# radio_oled.net
KiCad netlist of a schematic drawn in EAGLE
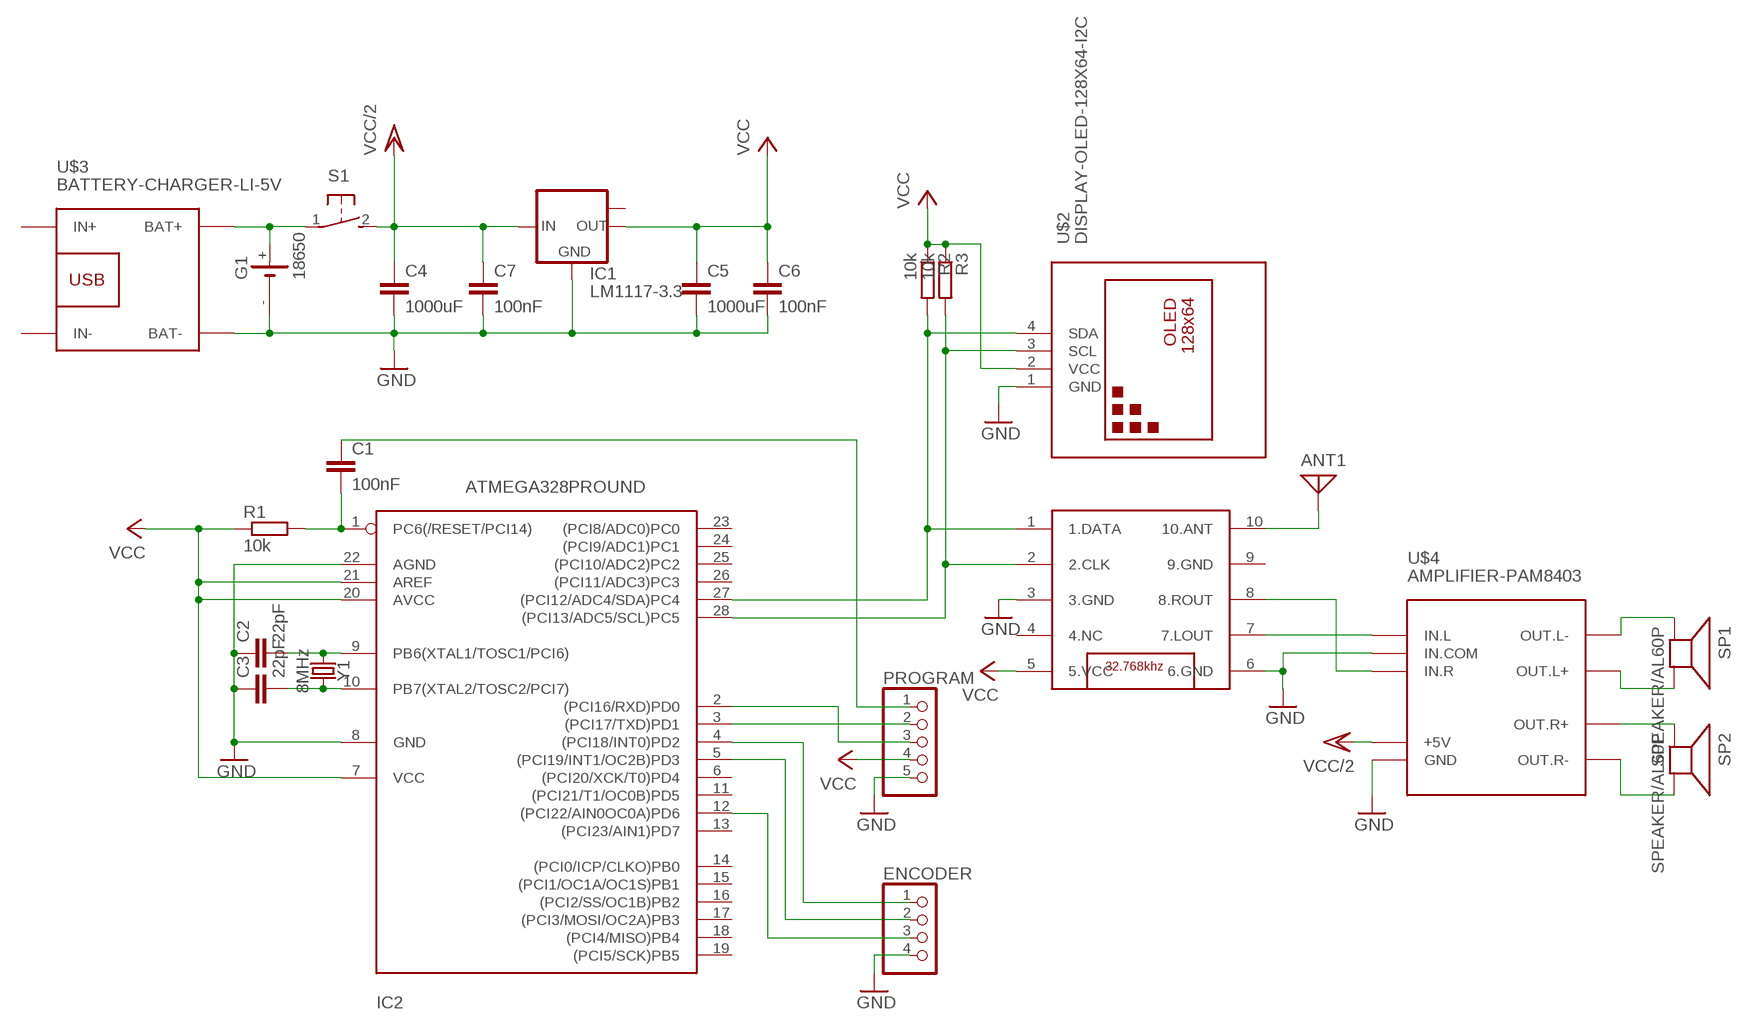
[diagram p0: schematic, sheet 1]

(export (version "E")
  (design (tool "Eeschema 10.0.6"))
  (components
    (comp (ref "ANT1")
      (value "ANTENNA")
      (footprint "eagle-import:PAD-01")
      (libsource (lib "eagle-import") (part "ANTENNA"))
    )
    (comp (ref "C1")
      (value "100nF")
      (footprint "eagle-import:C025-025X050")
      (libsource (lib "eagle-import") (part "C-EU025-025X050"))
    )
    (comp (ref "C2")
      (value "22pF")
      (footprint "eagle-import:C025-025X050")
      (libsource (lib "eagle-import") (part "C-EU025-025X050"))
    )
    (comp (ref "C3")
      (value "22pF")
      (footprint "eagle-import:C025-025X050")
      (libsource (lib "eagle-import") (part "C-EU025-025X050"))
    )
    (comp (ref "C4")
      (value "1000uF")
      (footprint "eagle-import:C025-025X050")
      (libsource (lib "eagle-import") (part "C-EU025-025X050"))
    )
    (comp (ref "C5")
      (value "1000uF")
      (footprint "eagle-import:C025-025X050")
      (libsource (lib "eagle-import") (part "C-EU025-025X050"))
    )
    (comp (ref "C6")
      (value "100nF")
      (footprint "eagle-import:C025-025X050")
      (libsource (lib "eagle-import") (part "C-EU025-025X050"))
    )
    (comp (ref "C7")
      (value "100nF")
      (footprint "eagle-import:C025-025X050")
      (libsource (lib "eagle-import") (part "C-EU025-025X050"))
    )
    (comp (ref "ENCODER")
      (value "PINHD-1X4")
      (footprint "eagle-import:1X04")
      (libsource (lib "eagle-import") (part "PINHD-1X4"))
    )
    (comp (ref "G1")
      (value "18650")
      (footprint "eagle-import:SL-160AA_PT")
      (libsource (lib "eagle-import") (part "SL-160AA/PT"))
    )
    (comp (ref "IC1")
      (value "LM1117-3.3")
      (footprint "eagle-import:SOT223")
      (libsource (lib "eagle-import") (part "LM1117IMPX-3.3"))
    )
    (comp (ref "IC2")
      (value "ATMEGA328PROUND")
      (footprint "eagle-import:DIL28-3-ROUND")
      (libsource (lib "eagle-import") (part "ATMEGA328PROUND"))
    )
    (comp (ref "PROGRAM")
      (value "PINHD-1X5")
      (footprint "eagle-import:1X05")
      (libsource (lib "eagle-import") (part "PINHD-1X5"))
    )
    (comp (ref "R1")
      (value "10k")
      (footprint "eagle-import:0204_7")
      (libsource (lib "eagle-import") (part "R-EU_0204/7"))
    )
    (comp (ref "R2")
      (value "10k")
      (footprint "eagle-import:0204_7")
      (libsource (lib "eagle-import") (part "R-EU_0204/7"))
    )
    (comp (ref "R3")
      (value "10k")
      (footprint "eagle-import:0204_7")
      (libsource (lib "eagle-import") (part "R-EU_0204/7"))
    )
    (comp (ref "S1")
      (value "31-XX")
      (footprint "eagle-import:B3F-31XX")
      (libsource (lib "eagle-import") (part "31-XX"))
    )
    (comp (ref "SP1")
      (value "SPEAKER/AL60P")
      (footprint "eagle-import:AL60P")
      (libsource (lib "eagle-import") (part "SPEAKER/AL60P"))
    )
    (comp (ref "SP2")
      (value "SPEAKER/AL60P")
      (footprint "eagle-import:AL60P")
      (libsource (lib "eagle-import") (part "SPEAKER/AL60P"))
    )
    (comp (ref "U$1")
      (value "TEA5767")
      (footprint "eagle-import:TJ-102BC")
      (libsource (lib "eagle-import") (part "TEA5767"))
    )
    (comp (ref "U$2")
      (value "DISPLAY-OLED-128X64-I2C")
      (footprint "eagle-import:DISPLAY-OLED-128X64-I2C")
      (libsource (lib "eagle-import") (part "DISPLAY-OLED-128X64-I2C"))
    )
    (comp (ref "U$3")
      (value "BATTERY-CHARGER-LI-5V")
      (footprint "eagle-import:BATTERY-CHARGER-LI-5V")
      (libsource (lib "eagle-import") (part "BATTERY-CHARGER-LI-5V"))
    )
    (comp (ref "U$4")
      (value "AMPLIFIER-PAM8403")
      (footprint "eagle-import:AMPLIFIER-PAM8403")
      (libsource (lib "eagle-import") (part "AMPLIFIER-PAM8403"))
    )
    (comp (ref "Y1")
      (value "8MHz")
      (footprint "eagle-import:HC49UP")
      (libsource (lib "eagle-import") (part "CRYSTAL-8MHZSMD-HC49UP"))
    )
  )
  (nets
    (net (code "1") (name "GND") (class "Default")
      (node (ref "C2") (pin "1") (pinfunction "1_1") (pintype "passive"))
      (node (ref "C3") (pin "1") (pinfunction "1_1") (pintype "passive"))
      (node (ref "C4") (pin "2") (pinfunction "2_2") (pintype "passive"))
      (node (ref "C5") (pin "2") (pinfunction "2_2") (pintype "passive"))
      (node (ref "C6") (pin "2") (pinfunction "2_2") (pintype "passive"))
      (node (ref "C7") (pin "2") (pinfunction "2_2") (pintype "passive"))
      (node (ref "ENCODER") (pin "4") (pinfunction "4_4") (pintype "passive"))
      (node (ref "G1") (pin "-") (pinfunction "-_-") (pintype "passive"))
      (node (ref "IC1") (pin "1") (pinfunction "GND_1") (pintype "input"))
      (node (ref "IC2") (pin "22") (pinfunction "AGND_22") (pintype "bidirectional"))
      (node (ref "IC2") (pin "8") (pinfunction "GND_8") (pintype "bidirectional"))
      (node (ref "PROGRAM") (pin "5") (pinfunction "5_5") (pintype "passive"))
      (node (ref "U$1") (pin "3") (pinfunction "3.GND_3") (pintype "bidirectional"))
      (node (ref "U$1") (pin "6") (pinfunction "6.GND_6") (pintype "bidirectional"))
      (node (ref "U$2") (pin "1") (pinfunction "GND_1") (pintype "power_in"))
      (node (ref "U$3") (pin "BAT-") (pinfunction "BAT-_BAT-") (pintype "bidirectional"))
      (node (ref "U$4") (pin "GND") (pinfunction "GND_GND") (pintype "power_in"))
      (node (ref "U$4") (pin "IN.COM") (pinfunction "IN.COM_IN.COM") (pintype "input"))
    )
    (net (code "2") (name "Net-(C1-Pad1)") (class "Default")
      (node (ref "C1") (pin "1") (pinfunction "1_1") (pintype "passive"))
      (node (ref "PROGRAM") (pin "1") (pinfunction "1_1") (pintype "passive"))
    )
    (net (code "3") (name "Net-(IC2-(PCI12{slash}ADC4{slash}SDA)PC4)") (class "Default")
      (node (ref "IC2") (pin "27") (pinfunction "(PCI12/ADC4/SDA)PC4_27") (pintype "bidirectional"))
      (node (ref "R2") (pin "2") (pinfunction "2_2") (pintype "passive"))
      (node (ref "U$1") (pin "1") (pinfunction "1.DATA_1") (pintype "bidirectional"))
      (node (ref "U$2") (pin "4") (pinfunction "SDA_4") (pintype "bidirectional"))
    )
    (net (code "4") (name "Net-(IC2-(PCI13{slash}ADC5{slash}SCL)PC5)") (class "Default")
      (node (ref "IC2") (pin "28") (pinfunction "(PCI13/ADC5/SCL)PC5_28") (pintype "bidirectional"))
      (node (ref "R3") (pin "2") (pinfunction "2_2") (pintype "passive"))
      (node (ref "U$1") (pin "2") (pinfunction "2.CLK_2") (pintype "bidirectional"))
      (node (ref "U$2") (pin "3") (pinfunction "SCL_3") (pintype "bidirectional"))
    )
    (net (code "5") (name "Net-(IC2-(PCI16{slash}RXD)PD0)") (class "Default")
      (node (ref "IC2") (pin "2") (pinfunction "(PCI16/RXD)PD0_2") (pintype "bidirectional"))
      (node (ref "PROGRAM") (pin "3") (pinfunction "3_3") (pintype "passive"))
    )
    (net (code "6") (name "Net-(IC2-(PCI17{slash}TXD)PD1)") (class "Default")
      (node (ref "IC2") (pin "3") (pinfunction "(PCI17/TXD)PD1_3") (pintype "bidirectional"))
      (node (ref "PROGRAM") (pin "2") (pinfunction "2_2") (pintype "passive"))
    )
    (net (code "7") (name "Net-(IC2-(PCI18{slash}INT0)PD2)") (class "Default")
      (node (ref "ENCODER") (pin "1") (pinfunction "1_1") (pintype "passive"))
      (node (ref "IC2") (pin "4") (pinfunction "(PCI18/INT0)PD2_4") (pintype "bidirectional"))
    )
    (net (code "8") (name "Net-(IC2-(PCI19{slash}INT1{slash}OC2B)PD3)") (class "Default")
      (node (ref "ENCODER") (pin "2") (pinfunction "2_2") (pintype "passive"))
      (node (ref "IC2") (pin "5") (pinfunction "(PCI19/INT1/OC2B)PD3_5") (pintype "bidirectional"))
    )
    (net (code "9") (name "Net-(IC2-(PCI22{slash}AIN0OC0A)PD6)") (class "Default")
      (node (ref "ENCODER") (pin "3") (pinfunction "3_3") (pintype "passive"))
      (node (ref "IC2") (pin "12") (pinfunction "(PCI22/AIN0OC0A)PD6_12") (pintype "bidirectional"))
    )
    (net (code "10") (name "Net-(IC2-PB6(XTAL1{slash}TOSC1{slash}PCI6))") (class "Default")
      (node (ref "C2") (pin "2") (pinfunction "2_2") (pintype "passive"))
      (node (ref "IC2") (pin "9") (pinfunction "PB6(XTAL1/TOSC1/PCI6)_9") (pintype "bidirectional"))
      (node (ref "Y1") (pin "1") (pinfunction "1_1") (pintype "passive"))
    )
    (net (code "11") (name "Net-(IC2-PB7(XTAL2{slash}TOSC2{slash}PCI7))") (class "Default")
      (node (ref "C3") (pin "2") (pinfunction "2_2") (pintype "passive"))
      (node (ref "IC2") (pin "10") (pinfunction "PB7(XTAL2/TOSC2/PCI7)_10") (pintype "bidirectional"))
      (node (ref "Y1") (pin "2") (pinfunction "2_2") (pintype "passive"))
    )
    (net (code "12") (name "Net-(IC2-PC6({slash}RESET{slash}PCI14))") (class "Default")
      (node (ref "C1") (pin "2") (pinfunction "2_2") (pintype "passive"))
      (node (ref "IC2") (pin "1") (pinfunction "PC6(/RESET/PCI14)_1") (pintype "bidirectional"))
      (node (ref "R1") (pin "2") (pinfunction "2_2") (pintype "passive"))
    )
    (net (code "13") (name "Net-(S1-P)") (class "Default")
      (node (ref "G1") (pin "+") (pinfunction "+_+") (pintype "passive"))
      (node (ref "S1") (pin "1") (pinfunction "P_1") (pintype "passive"))
      (node (ref "U$3") (pin "BAT+") (pinfunction "BAT+_BAT+") (pintype "bidirectional"))
    )
    (net (code "14") (name "Net-(SP1-+)") (class "Default")
      (node (ref "SP1") (pin "1") (pinfunction "+_1") (pintype "passive"))
      (node (ref "U$4") (pin "OUT.L-") (pinfunction "OUT.L-_OUT.L-") (pintype "output"))
    )
    (net (code "15") (name "Net-(SP1--)") (class "Default")
      (node (ref "SP1") (pin "2") (pinfunction "-_2") (pintype "passive"))
      (node (ref "U$4") (pin "OUT.L+") (pinfunction "OUT.L+_OUT.L+") (pintype "output"))
    )
    (net (code "16") (name "Net-(SP2-+)") (class "Default")
      (node (ref "SP2") (pin "1") (pinfunction "+_1") (pintype "passive"))
      (node (ref "U$4") (pin "OUT.R+") (pinfunction "OUT.R+_OUT.R+") (pintype "output"))
    )
    (net (code "17") (name "Net-(SP2--)") (class "Default")
      (node (ref "SP2") (pin "2") (pinfunction "-_2") (pintype "passive"))
      (node (ref "U$4") (pin "OUT.R-") (pinfunction "OUT.R-_OUT.R-") (pintype "output"))
    )
    (net (code "18") (name "Net-(U$1-7.LOUT)") (class "Default")
      (node (ref "U$1") (pin "7") (pinfunction "7.LOUT_7") (pintype "bidirectional"))
      (node (ref "U$4") (pin "IN.L") (pinfunction "IN.L_IN.L") (pintype "input"))
    )
    (net (code "19") (name "Net-(U$1-8.ROUT)") (class "Default")
      (node (ref "U$1") (pin "8") (pinfunction "8.ROUT_8") (pintype "bidirectional"))
      (node (ref "U$4") (pin "IN.R") (pinfunction "IN.R_IN.R") (pintype "bidirectional"))
    )
    (net (code "20") (name "Net-(U$1-10.ANT)") (class "Default")
      (node (ref "ANT1") (pin "1") (pinfunction "1_1") (pintype "output"))
      (node (ref "U$1") (pin "10") (pinfunction "10.ANT_10") (pintype "bidirectional"))
    )
    (net (code "21") (name "VCC") (class "Default")
      (node (ref "C5") (pin "1") (pinfunction "1_1") (pintype "passive"))
      (node (ref "C6") (pin "1") (pinfunction "1_1") (pintype "passive"))
      (node (ref "IC1") (pin "2") (pinfunction "OUT_2") (pintype "passive"))
      (node (ref "IC2") (pin "20") (pinfunction "AVCC_20") (pintype "bidirectional"))
      (node (ref "IC2") (pin "21") (pinfunction "AREF_21") (pintype "bidirectional"))
      (node (ref "IC2") (pin "7") (pinfunction "VCC_7") (pintype "bidirectional"))
      (node (ref "PROGRAM") (pin "4") (pinfunction "4_4") (pintype "passive"))
      (node (ref "R1") (pin "1") (pinfunction "1_1") (pintype "passive"))
      (node (ref "R2") (pin "1") (pinfunction "1_1") (pintype "passive"))
      (node (ref "R3") (pin "1") (pinfunction "1_1") (pintype "passive"))
      (node (ref "U$1") (pin "5") (pinfunction "5.VCC_5") (pintype "bidirectional"))
      (node (ref "U$2") (pin "2") (pinfunction "VCC_2") (pintype "power_in"))
    )
    (net (code "22") (name "VCC{slash}2") (class "Default")
      (node (ref "C4") (pin "1") (pinfunction "1_1") (pintype "passive"))
      (node (ref "C7") (pin "1") (pinfunction "1_1") (pintype "passive"))
      (node (ref "IC1") (pin "3") (pinfunction "IN_3") (pintype "input"))
      (node (ref "S1") (pin "2") (pinfunction "S_2") (pintype "passive"))
      (node (ref "U$4") (pin "+5V") (pinfunction "+5V_+5V") (pintype "power_in"))
    )
    (net (code "23") (name "unconnected-(G1---Pad-@1)") (class "Default")
      (node (ref "G1") (pin "-@1") (pinfunction "-_-@1") (pintype "passive"))
    )
    (net (code "24") (name "unconnected-(IC1-OUT1-PadTAB)") (class "Default")
      (node (ref "IC1") (pin "TAB") (pinfunction "OUT1_TAB") (pintype "passive"))
    )
    (net (code "25") (name "unconnected-(IC2-(PCI0{slash}ICP{slash}CLKO)PB0-Pad14)") (class "Default")
      (node (ref "IC2") (pin "14") (pinfunction "(PCI0/ICP/CLKO)PB0_14") (pintype "bidirectional"))
    )
    (net (code "26") (name "unconnected-(IC2-(PCI1{slash}OC1A{slash}OC1S)PB1-Pad15)") (class "Default")
      (node (ref "IC2") (pin "15") (pinfunction "(PCI1/OC1A/OC1S)PB1_15") (pintype "bidirectional"))
    )
    (net (code "27") (name "unconnected-(IC2-(PCI2{slash}SS{slash}OC1B)PB2-Pad16)") (class "Default")
      (node (ref "IC2") (pin "16") (pinfunction "(PCI2/SS/OC1B)PB2_16") (pintype "bidirectional"))
    )
    (net (code "28") (name "unconnected-(IC2-(PCI3{slash}MOSI{slash}OC2A)PB3-Pad17)") (class "Default")
      (node (ref "IC2") (pin "17") (pinfunction "(PCI3/MOSI/OC2A)PB3_17") (pintype "bidirectional"))
    )
    (net (code "29") (name "unconnected-(IC2-(PCI4{slash}MISO)PB4-Pad18)") (class "Default")
      (node (ref "IC2") (pin "18") (pinfunction "(PCI4/MISO)PB4_18") (pintype "bidirectional"))
    )
    (net (code "30") (name "unconnected-(IC2-(PCI5{slash}SCK)PB5-Pad19)") (class "Default")
      (node (ref "IC2") (pin "19") (pinfunction "(PCI5/SCK)PB5_19") (pintype "bidirectional"))
    )
    (net (code "31") (name "unconnected-(IC2-(PCI8{slash}ADC0)PC0-Pad23)") (class "Default")
      (node (ref "IC2") (pin "23") (pinfunction "(PCI8/ADC0)PC0_23") (pintype "bidirectional"))
    )
    (net (code "32") (name "unconnected-(IC2-(PCI9{slash}ADC1)PC1-Pad24)") (class "Default")
      (node (ref "IC2") (pin "24") (pinfunction "(PCI9/ADC1)PC1_24") (pintype "bidirectional"))
    )
    (net (code "33") (name "unconnected-(IC2-(PCI10{slash}ADC2)PC2-Pad25)") (class "Default")
      (node (ref "IC2") (pin "25") (pinfunction "(PCI10/ADC2)PC2_25") (pintype "bidirectional"))
    )
    (net (code "34") (name "unconnected-(IC2-(PCI11{slash}ADC3)PC3-Pad26)") (class "Default")
      (node (ref "IC2") (pin "26") (pinfunction "(PCI11/ADC3)PC3_26") (pintype "bidirectional"))
    )
    (net (code "35") (name "unconnected-(IC2-(PCI20{slash}XCK{slash}T0)PD4-Pad6)") (class "Default")
      (node (ref "IC2") (pin "6") (pinfunction "(PCI20/XCK/T0)PD4_6") (pintype "bidirectional"))
    )
    (net (code "36") (name "unconnected-(IC2-(PCI21{slash}T1{slash}OC0B)PD5-Pad11)") (class "Default")
      (node (ref "IC2") (pin "11") (pinfunction "(PCI21/T1/OC0B)PD5_11") (pintype "bidirectional"))
    )
    (net (code "37") (name "unconnected-(IC2-(PCI23{slash}AIN1)PD7-Pad13)") (class "Default")
      (node (ref "IC2") (pin "13") (pinfunction "(PCI23/AIN1)PD7_13") (pintype "bidirectional"))
    )
    (net (code "38") (name "unconnected-(U$1-4.NC-Pad4)") (class "Default")
      (node (ref "U$1") (pin "4") (pinfunction "4.NC_4") (pintype "bidirectional"))
    )
    (net (code "39") (name "unconnected-(U$1-9.GND-Pad9)") (class "Default")
      (node (ref "U$1") (pin "9") (pinfunction "9.GND_9") (pintype "bidirectional"))
    )
    (net (code "40") (name "unconnected-(U$3-PadIN+)") (class "Default")
      (node (ref "U$3") (pin "IN+") (pinfunction "IN+_IN+") (pintype "bidirectional"))
    )
    (net (code "41") (name "unconnected-(U$3-PadIN-)") (class "Default")
      (node (ref "U$3") (pin "IN-") (pinfunction "IN-_IN-") (pintype "bidirectional"))
    )
  )
)
